# Mounting_PCB_A.net
KiCad netlist of a schematic drawn in Altium Designer
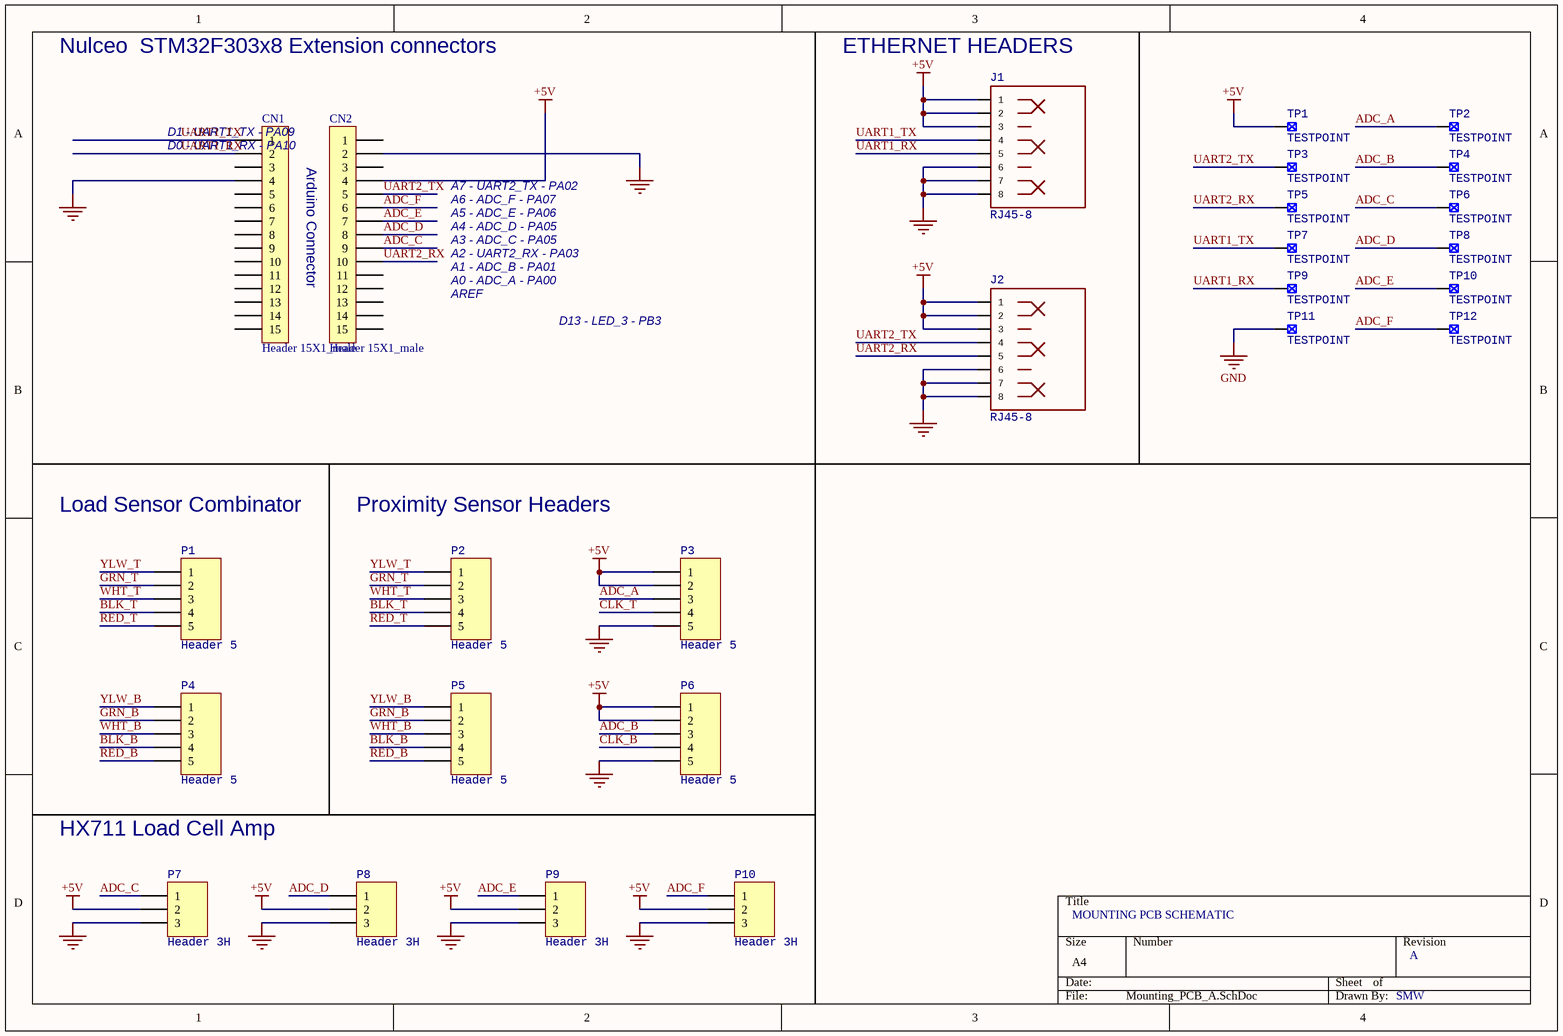
[diagram p0: Mounting_PCB_A.SchDoc]

(export (version "E")
  (design (tool "Eeschema 10.0.6"))
  (components
    (comp (ref "CN1")
      (value "Header 15X1_male")
      (footprint "HDR_1x15_2R54_V_F")
      (description "Header, 10-Pin, Single row,female")
      (fields (field (name "PUBLISHER") "Altium Limited"))
      (libsource (lib "MB1180") (part "Header 15X1_Female_1"))
    )
    (comp (ref "CN2")
      (value "Header 15X1_male")
      (footprint "HDR_1x15_2R54_V_F")
      (description "Header, 10-Pin, Single row,female")
      (fields (field (name "PUBLISHER") "Altium Limited"))
      (libsource (lib "") (part "Header 15X1_Female_1_1"))
    )
    (comp (ref "J1")
      (value "RJ45-8")
      (footprint "RJ45-8")
      (libsource (lib "SparkFun-Connectors") (part "RJ45-8"))
    )
    (comp (ref "J2")
      (value "RJ45-8")
      (footprint "RJ45-8")
      (libsource (lib "SparkFun-Connectors") (part "RJ45-8"))
    )
    (comp (ref "P1")
      (value "Header 5")
      (footprint "HDR1X5")
      (description "Header, 5-Pin")
      (fields (field (name "PUBLISHER") "Altium Limited"))
      (libsource (lib "Miscellaneous Connectors") (part "Header 5"))
    )
    (comp (ref "P2")
      (value "Header 5")
      (footprint "HDR1X5")
      (description "Header, 5-Pin")
      (fields (field (name "PUBLISHER") "Altium Limited"))
      (libsource (lib "Miscellaneous Connectors") (part "Header 5"))
    )
    (comp (ref "P3")
      (value "Header 5")
      (footprint "HDR1X5")
      (description "Header, 5-Pin")
      (fields (field (name "PUBLISHER") "Altium Limited"))
      (libsource (lib "Miscellaneous Connectors") (part "Header 5"))
    )
    (comp (ref "P4")
      (value "Header 5")
      (footprint "HDR1X5")
      (description "Header, 5-Pin")
      (fields (field (name "PUBLISHER") "Altium Limited"))
      (libsource (lib "Miscellaneous Connectors") (part "Header 5"))
    )
    (comp (ref "P5")
      (value "Header 5")
      (footprint "HDR1X5")
      (description "Header, 5-Pin")
      (fields (field (name "PUBLISHER") "Altium Limited"))
      (libsource (lib "Miscellaneous Connectors") (part "Header 5"))
    )
    (comp (ref "P6")
      (value "Header 5")
      (footprint "HDR1X5")
      (description "Header, 5-Pin")
      (fields (field (name "PUBLISHER") "Altium Limited"))
      (libsource (lib "Miscellaneous Connectors") (part "Header 5"))
    )
    (comp (ref "P7")
      (value "Header 3H")
      (footprint "HDR1X3H")
      (description "Header, 3-Pin, Right Angle")
      (fields (field (name "PUBLISHER") "Altium Limited"))
      (libsource (lib "Miscellaneous Connectors") (part "Header 3H"))
    )
    (comp (ref "P8")
      (value "Header 3H")
      (footprint "HDR1X3H")
      (description "Header, 3-Pin, Right Angle")
      (fields (field (name "PUBLISHER") "Altium Limited"))
      (libsource (lib "Miscellaneous Connectors") (part "Header 3H"))
    )
    (comp (ref "P9")
      (value "Header 3H")
      (footprint "HDR1X3H")
      (description "Header, 3-Pin, Right Angle")
      (fields (field (name "PUBLISHER") "Altium Limited"))
      (libsource (lib "Miscellaneous Connectors") (part "Header 3H"))
    )
    (comp (ref "P10")
      (value "Header 3H")
      (footprint "HDR1X3H")
      (description "Header, 3-Pin, Right Angle")
      (fields (field (name "PUBLISHER") "Altium Limited"))
      (libsource (lib "Miscellaneous Connectors") (part "Header 3H"))
    )
    (comp (ref "TP1")
      (value "TESTPOINT")
      (footprint "TP70")
      (description "Test Point")
      (libsource (lib "KBsch01") (part "TESTPOINT"))
    )
    (comp (ref "TP2")
      (value "TESTPOINT")
      (footprint "TP70")
      (description "Test Point")
      (libsource (lib "KBsch01") (part "TESTPOINT"))
    )
    (comp (ref "TP3")
      (value "TESTPOINT")
      (footprint "TP70")
      (description "Test Point")
      (libsource (lib "KBsch01") (part "TESTPOINT"))
    )
    (comp (ref "TP4")
      (value "TESTPOINT")
      (footprint "TP70")
      (description "Test Point")
      (libsource (lib "KBsch01") (part "TESTPOINT"))
    )
    (comp (ref "TP5")
      (value "TESTPOINT")
      (footprint "TP70")
      (description "Test Point")
      (libsource (lib "KBsch01") (part "TESTPOINT"))
    )
    (comp (ref "TP6")
      (value "TESTPOINT")
      (footprint "TP70")
      (description "Test Point")
      (libsource (lib "KBsch01") (part "TESTPOINT"))
    )
    (comp (ref "TP7")
      (value "TESTPOINT")
      (footprint "TP70")
      (description "Test Point")
      (libsource (lib "KBsch01") (part "TESTPOINT"))
    )
    (comp (ref "TP8")
      (value "TESTPOINT")
      (footprint "TP70")
      (description "Test Point")
      (libsource (lib "KBsch01") (part "TESTPOINT"))
    )
    (comp (ref "TP9")
      (value "TESTPOINT")
      (footprint "TP70")
      (description "Test Point")
      (libsource (lib "KBsch01") (part "TESTPOINT"))
    )
    (comp (ref "TP10")
      (value "TESTPOINT")
      (footprint "TP70")
      (description "Test Point")
      (libsource (lib "KBsch01") (part "TESTPOINT"))
    )
    (comp (ref "TP11")
      (value "TESTPOINT")
      (footprint "TP70")
      (description "Test Point")
      (libsource (lib "KBsch01") (part "TESTPOINT"))
    )
    (comp (ref "TP12")
      (value "TESTPOINT")
      (footprint "TP70")
      (description "Test Point")
      (libsource (lib "KBsch01") (part "TESTPOINT"))
    )
  )
  (nets
    (net (code "1") (name "+5V") (class "Default")
      (node (ref "CN2") (pin "4") (pinfunction "4_4") (pintype "passive"))
      (node (ref "J1") (pin "1") (pinfunction "1_1") (pintype "passive"))
      (node (ref "J1") (pin "2") (pinfunction "2_2") (pintype "passive"))
      (node (ref "J1") (pin "3") (pinfunction "3_3") (pintype "passive"))
      (node (ref "J2") (pin "1") (pinfunction "1_1") (pintype "passive"))
      (node (ref "J2") (pin "2") (pinfunction "2_2") (pintype "passive"))
      (node (ref "J2") (pin "3") (pinfunction "3_3") (pintype "passive"))
      (node (ref "P10") (pin "2") (pinfunction "2_2") (pintype "passive"))
      (node (ref "P3") (pin "1") (pinfunction "1_1") (pintype "passive"))
      (node (ref "P3") (pin "2") (pinfunction "2_2") (pintype "passive"))
      (node (ref "P6") (pin "1") (pinfunction "1_1") (pintype "passive"))
      (node (ref "P6") (pin "2") (pinfunction "2_2") (pintype "passive"))
      (node (ref "P7") (pin "2") (pinfunction "2_2") (pintype "passive"))
      (node (ref "P8") (pin "2") (pinfunction "2_2") (pintype "passive"))
      (node (ref "P9") (pin "2") (pinfunction "2_2") (pintype "passive"))
      (node (ref "TP1") (pin "1") (pintype "passive"))
    )
    (net (code "2") (name "/ADC_A") (class "Default")
      (node (ref "P3") (pin "3") (pinfunction "3_3") (pintype "passive"))
      (node (ref "TP2") (pin "1") (pintype "passive"))
    )
    (net (code "3") (name "/ADC_B") (class "Default")
      (node (ref "P6") (pin "3") (pinfunction "3_3") (pintype "passive"))
      (node (ref "TP4") (pin "1") (pintype "passive"))
    )
    (net (code "4") (name "/ADC_C") (class "Default")
      (node (ref "CN2") (pin "9") (pinfunction "9_9") (pintype "passive"))
      (node (ref "P7") (pin "1") (pinfunction "1_1") (pintype "passive"))
      (node (ref "TP6") (pin "1") (pintype "passive"))
    )
    (net (code "5") (name "/ADC_D") (class "Default")
      (node (ref "CN2") (pin "8") (pinfunction "8_8") (pintype "passive"))
      (node (ref "P8") (pin "1") (pinfunction "1_1") (pintype "passive"))
      (node (ref "TP8") (pin "1") (pintype "passive"))
    )
    (net (code "6") (name "/ADC_E") (class "Default")
      (node (ref "CN2") (pin "7") (pinfunction "7_7") (pintype "passive"))
      (node (ref "P9") (pin "1") (pinfunction "1_1") (pintype "passive"))
      (node (ref "TP10") (pin "1") (pintype "passive"))
    )
    (net (code "7") (name "/ADC_F") (class "Default")
      (node (ref "CN2") (pin "6") (pinfunction "6_6") (pintype "passive"))
      (node (ref "P10") (pin "1") (pinfunction "1_1") (pintype "passive"))
      (node (ref "TP12") (pin "1") (pintype "passive"))
    )
    (net (code "8") (name "/BLK_B") (class "Default")
      (node (ref "P4") (pin "4") (pinfunction "4_4") (pintype "passive"))
      (node (ref "P5") (pin "4") (pinfunction "4_4") (pintype "passive"))
    )
    (net (code "9") (name "/BLK_T") (class "Default")
      (node (ref "P1") (pin "4") (pinfunction "4_4") (pintype "passive"))
      (node (ref "P2") (pin "4") (pinfunction "4_4") (pintype "passive"))
    )
    (net (code "10") (name "/CLK_B") (class "Default")
      (node (ref "P6") (pin "4") (pinfunction "4_4") (pintype "passive"))
    )
    (net (code "11") (name "/CLK_T") (class "Default")
      (node (ref "P3") (pin "4") (pinfunction "4_4") (pintype "passive"))
    )
    (net (code "12") (name "/GRN_B") (class "Default")
      (node (ref "P4") (pin "2") (pinfunction "2_2") (pintype "passive"))
      (node (ref "P5") (pin "2") (pinfunction "2_2") (pintype "passive"))
    )
    (net (code "13") (name "/GRN_T") (class "Default")
      (node (ref "P1") (pin "2") (pinfunction "2_2") (pintype "passive"))
      (node (ref "P2") (pin "2") (pinfunction "2_2") (pintype "passive"))
    )
    (net (code "14") (name "/RED_B") (class "Default")
      (node (ref "P4") (pin "5") (pinfunction "5_5") (pintype "passive"))
      (node (ref "P5") (pin "5") (pinfunction "5_5") (pintype "passive"))
    )
    (net (code "15") (name "/RED_T") (class "Default")
      (node (ref "P1") (pin "5") (pinfunction "5_5") (pintype "passive"))
      (node (ref "P2") (pin "5") (pinfunction "5_5") (pintype "passive"))
    )
    (net (code "16") (name "/UART1_RX") (class "Default")
      (node (ref "CN1") (pin "2") (pinfunction "2_2") (pintype "passive"))
      (node (ref "J1") (pin "5") (pinfunction "5_5") (pintype "passive"))
      (node (ref "TP9") (pin "1") (pintype "passive"))
    )
    (net (code "17") (name "/UART1_TX") (class "Default")
      (node (ref "CN1") (pin "1") (pinfunction "1_1") (pintype "passive"))
      (node (ref "J1") (pin "4") (pinfunction "4_4") (pintype "passive"))
      (node (ref "TP7") (pin "1") (pintype "passive"))
    )
    (net (code "18") (name "/UART2_RX") (class "Default")
      (node (ref "CN2") (pin "10") (pinfunction "10_10") (pintype "passive"))
      (node (ref "J2") (pin "5") (pinfunction "5_5") (pintype "passive"))
      (node (ref "TP5") (pin "1") (pintype "passive"))
    )
    (net (code "19") (name "/UART2_TX") (class "Default")
      (node (ref "CN2") (pin "5") (pinfunction "5_5") (pintype "passive"))
      (node (ref "J2") (pin "4") (pinfunction "4_4") (pintype "passive"))
      (node (ref "TP3") (pin "1") (pintype "passive"))
    )
    (net (code "20") (name "/WHT_B") (class "Default")
      (node (ref "P4") (pin "3") (pinfunction "3_3") (pintype "passive"))
      (node (ref "P5") (pin "3") (pinfunction "3_3") (pintype "passive"))
    )
    (net (code "21") (name "/WHT_T") (class "Default")
      (node (ref "P1") (pin "3") (pinfunction "3_3") (pintype "passive"))
      (node (ref "P2") (pin "3") (pinfunction "3_3") (pintype "passive"))
    )
    (net (code "22") (name "/YLW_B") (class "Default")
      (node (ref "P4") (pin "1") (pinfunction "1_1") (pintype "passive"))
      (node (ref "P5") (pin "1") (pinfunction "1_1") (pintype "passive"))
    )
    (net (code "23") (name "/YLW_T") (class "Default")
      (node (ref "P1") (pin "1") (pinfunction "1_1") (pintype "passive"))
      (node (ref "P2") (pin "1") (pinfunction "1_1") (pintype "passive"))
    )
    (net (code "24") (name "GND") (class "Default")
      (node (ref "CN1") (pin "4") (pinfunction "4_4") (pintype "passive"))
      (node (ref "CN2") (pin "2") (pinfunction "2_2") (pintype "passive"))
      (node (ref "J1") (pin "6") (pinfunction "6_6") (pintype "passive"))
      (node (ref "J1") (pin "7") (pinfunction "7_7") (pintype "passive"))
      (node (ref "J1") (pin "8") (pinfunction "8_8") (pintype "passive"))
      (node (ref "J2") (pin "6") (pinfunction "6_6") (pintype "passive"))
      (node (ref "J2") (pin "7") (pinfunction "7_7") (pintype "passive"))
      (node (ref "J2") (pin "8") (pinfunction "8_8") (pintype "passive"))
      (node (ref "P10") (pin "3") (pinfunction "3_3") (pintype "passive"))
      (node (ref "P3") (pin "5") (pinfunction "5_5") (pintype "passive"))
      (node (ref "P6") (pin "5") (pinfunction "5_5") (pintype "passive"))
      (node (ref "P7") (pin "3") (pinfunction "3_3") (pintype "passive"))
      (node (ref "P8") (pin "3") (pinfunction "3_3") (pintype "passive"))
      (node (ref "P9") (pin "3") (pinfunction "3_3") (pintype "passive"))
      (node (ref "TP11") (pin "1") (pintype "passive"))
    )
    (net (code "25") (name "unconnected-(CN1-Pad3)") (class "Default")
      (node (ref "CN1") (pin "3") (pinfunction "3_3") (pintype "passive"))
    )
    (net (code "26") (name "unconnected-(CN1-Pad5)") (class "Default")
      (node (ref "CN1") (pin "5") (pinfunction "5_5") (pintype "passive"))
    )
    (net (code "27") (name "unconnected-(CN1-Pad6)") (class "Default")
      (node (ref "CN1") (pin "6") (pinfunction "6_6") (pintype "passive"))
    )
    (net (code "28") (name "unconnected-(CN1-Pad7)") (class "Default")
      (node (ref "CN1") (pin "7") (pinfunction "7_7") (pintype "passive"))
    )
    (net (code "29") (name "unconnected-(CN1-Pad8)") (class "Default")
      (node (ref "CN1") (pin "8") (pinfunction "8_8") (pintype "passive"))
    )
    (net (code "30") (name "unconnected-(CN1-Pad9)") (class "Default")
      (node (ref "CN1") (pin "9") (pinfunction "9_9") (pintype "passive"))
    )
    (net (code "31") (name "unconnected-(CN1-Pad10)") (class "Default")
      (node (ref "CN1") (pin "10") (pinfunction "10_10") (pintype "passive"))
    )
    (net (code "32") (name "unconnected-(CN1-Pad11)") (class "Default")
      (node (ref "CN1") (pin "11") (pinfunction "11_11") (pintype "passive"))
    )
    (net (code "33") (name "unconnected-(CN1-Pad12)") (class "Default")
      (node (ref "CN1") (pin "12") (pinfunction "12_12") (pintype "passive"))
    )
    (net (code "34") (name "unconnected-(CN1-Pad13)") (class "Default")
      (node (ref "CN1") (pin "13") (pinfunction "13_13") (pintype "passive"))
    )
    (net (code "35") (name "unconnected-(CN1-Pad14)") (class "Default")
      (node (ref "CN1") (pin "14") (pinfunction "14_14") (pintype "passive"))
    )
    (net (code "36") (name "unconnected-(CN1-Pad15)") (class "Default")
      (node (ref "CN1") (pin "15") (pinfunction "15_15") (pintype "passive"))
    )
    (net (code "37") (name "unconnected-(CN2-Pad1)") (class "Default")
      (node (ref "CN2") (pin "1") (pinfunction "1_1") (pintype "passive"))
    )
    (net (code "38") (name "unconnected-(CN2-Pad3)") (class "Default")
      (node (ref "CN2") (pin "3") (pinfunction "3_3") (pintype "passive"))
    )
    (net (code "39") (name "unconnected-(CN2-Pad11)") (class "Default")
      (node (ref "CN2") (pin "11") (pinfunction "11_11") (pintype "passive"))
    )
    (net (code "40") (name "unconnected-(CN2-Pad12)") (class "Default")
      (node (ref "CN2") (pin "12") (pinfunction "12_12") (pintype "passive"))
    )
    (net (code "41") (name "unconnected-(CN2-Pad13)") (class "Default")
      (node (ref "CN2") (pin "13") (pinfunction "13_13") (pintype "passive"))
    )
    (net (code "42") (name "unconnected-(CN2-Pad14)") (class "Default")
      (node (ref "CN2") (pin "14") (pinfunction "14_14") (pintype "passive"))
    )
    (net (code "43") (name "unconnected-(CN2-Pad15)") (class "Default")
      (node (ref "CN2") (pin "15") (pinfunction "15_15") (pintype "passive"))
    )
  )
)
